# Rover_Power_Supply.net
KiCad netlist of a schematic drawn in EAGLE
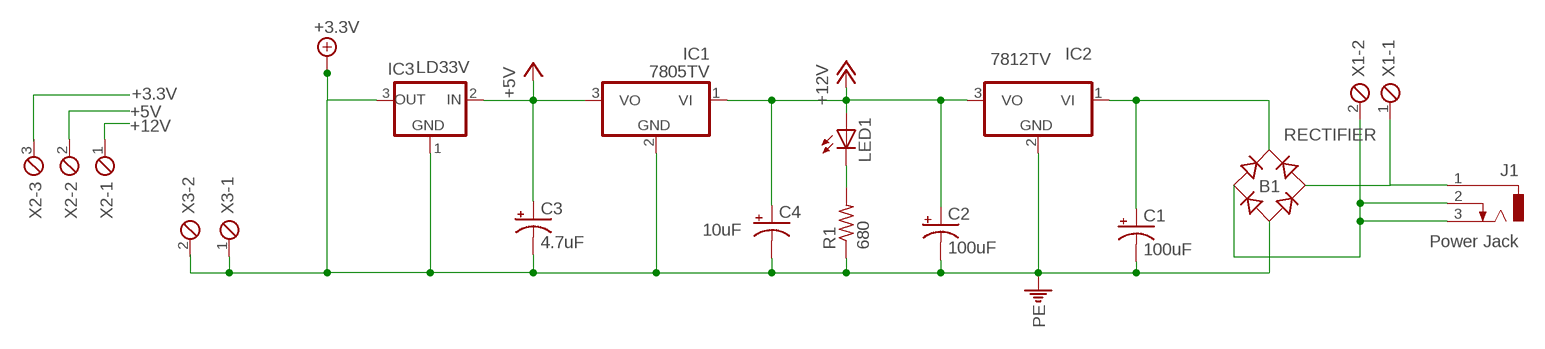
[diagram p0: schematic, sheet 1]

(export (version "E")
  (design (tool "Eeschema 10.0.6"))
  (components
    (comp (ref "B1")
      (value "RECTIFIER")
      (footprint "eagle-import:RB1A")
      (libsource (lib "eagle-import") (part "RB1A"))
    )
    (comp (ref "C1")
      (value "100uF")
      (footprint "eagle-import:E5-8,5")
      (libsource (lib "eagle-import") (part "CPOL-USE5-8.5"))
    )
    (comp (ref "C2")
      (value "100uF")
      (footprint "eagle-import:E5-8,5")
      (libsource (lib "eagle-import") (part "CPOL-USE5-8.5"))
    )
    (comp (ref "C3")
      (value "4.7uF")
      (footprint "eagle-import:E5-8,5")
      (libsource (lib "eagle-import") (part "CPOL-USE5-8.5"))
    )
    (comp (ref "C4")
      (value "10uF")
      (footprint "eagle-import:E5-8,5")
      (libsource (lib "eagle-import") (part "CPOL-USE5-8.5"))
    )
    (comp (ref "IC1")
      (value "7805TV")
      (footprint "eagle-import:TO220V")
      (libsource (lib "eagle-import") (part "78TV05"))
    )
    (comp (ref "IC2")
      (value "7812TV")
      (footprint "eagle-import:TO220V")
      (libsource (lib "eagle-import") (part "78TV12"))
    )
    (comp (ref "IC3")
      (value "LD33V")
      (footprint "eagle-import:78MXXS")
      (libsource (lib "eagle-import") (part "78MXXS"))
    )
    (comp (ref "J1")
      (value "Power Jack")
      (footprint "eagle-import:ROVER-PW-JACL")
      (libsource (lib "eagle-import") (part "DCJ0303"))
    )
    (comp (ref "LED1")
      (value "LED3MM")
      (footprint "eagle-import:LED3MM")
      (libsource (lib "eagle-import") (part "LED3MM"))
    )
    (comp (ref "R1")
      (value "680")
      (footprint "eagle-import:0204_5")
      (libsource (lib "eagle-import") (part "R-US_0204/5"))
    )
    (comp (ref "X1")
      (value "MPT2")
      (footprint "eagle-import:2POL254")
      (libsource (lib "eagle-import") (part "MPT2"))
    )
    (comp (ref "X2")
      (value "MPT3")
      (footprint "eagle-import:3POL254")
      (libsource (lib "eagle-import") (part "MPT3"))
    )
    (comp (ref "X3")
      (value "MPT2")
      (footprint "eagle-import:2POL254")
      (libsource (lib "eagle-import") (part "MPT2"))
    )
  )
  (nets
    (net (code "1") (name "+3.3V") (class "Default")
      (node (ref "B1") (pin "-") (pinfunction "-_-") (pintype "passive"))
      (node (ref "C1") (pin "-") (pinfunction "-_-") (pintype "passive"))
      (node (ref "C2") (pin "-") (pinfunction "-_-") (pintype "passive"))
      (node (ref "C3") (pin "-") (pinfunction "-_-") (pintype "passive"))
      (node (ref "C4") (pin "-") (pinfunction "-_-") (pintype "passive"))
      (node (ref "IC1") (pin "2") (pinfunction "GND_2") (pintype "passive"))
      (node (ref "IC2") (pin "2") (pinfunction "GND_2") (pintype "passive"))
      (node (ref "IC3") (pin "GND") (pinfunction "GND_GND") (pintype "input"))
      (node (ref "IC3") (pin "OUT") (pinfunction "OUT_OUT") (pintype "passive"))
      (node (ref "R1") (pin "1") (pinfunction "1_1") (pintype "passive"))
      (node (ref "X3") (pin "1") (pinfunction "1_1") (pintype "passive"))
    )
    (net (code "2") (name "+5V") (class "Default")
      (node (ref "C3") (pin "+") (pinfunction "+_+") (pintype "passive"))
      (node (ref "IC1") (pin "3") (pinfunction "VO_3") (pintype "passive"))
      (node (ref "X2") (pin "2") (pinfunction "1_2") (pintype "passive"))
    )
    (net (code "3") (name "+12V") (class "Default")
      (node (ref "C2") (pin "+") (pinfunction "+_+") (pintype "passive"))
      (node (ref "C4") (pin "+") (pinfunction "+_+") (pintype "passive"))
      (node (ref "IC1") (pin "1") (pinfunction "VI_1") (pintype "input"))
      (node (ref "IC2") (pin "3") (pinfunction "VO_3") (pintype "passive"))
      (node (ref "LED1") (pin "A") (pinfunction "A_A") (pintype "passive"))
      (node (ref "X2") (pin "1") (pinfunction "1_1") (pintype "passive"))
    )
    (net (code "4") (name "Net-(B1-PadAC1)") (class "Default")
      (node (ref "B1") (pin "AC1") (pinfunction "AC1_AC1") (pintype "passive"))
      (node (ref "J1") (pin "1") (pinfunction "1_1") (pintype "passive"))
      (node (ref "X1") (pin "1") (pinfunction "1_1") (pintype "passive"))
    )
    (net (code "5") (name "Net-(IC2-VI)") (class "Default")
      (node (ref "B1") (pin "+") (pinfunction "+_+") (pintype "passive"))
      (node (ref "C1") (pin "+") (pinfunction "+_+") (pintype "passive"))
      (node (ref "IC2") (pin "1") (pinfunction "VI_1") (pintype "input"))
    )
    (net (code "6") (name "Net-(LED1-C)") (class "Default")
      (node (ref "LED1") (pin "K") (pinfunction "C_K") (pintype "passive"))
      (node (ref "R1") (pin "2") (pinfunction "2_2") (pintype "passive"))
    )
    (net (code "7") (name "Net-(X1B-1)") (class "Default")
      (node (ref "B1") (pin "AC2") (pinfunction "AC2_AC2") (pintype "passive"))
      (node (ref "J1") (pin "2") (pinfunction "2_2") (pintype "passive"))
      (node (ref "J1") (pin "3") (pinfunction "3_3") (pintype "passive"))
      (node (ref "X1") (pin "2") (pinfunction "1_2") (pintype "passive"))
    )
    (net (code "8") (name "unconnected-(IC3-PadIN)") (class "Default")
      (node (ref "IC3") (pin "IN") (pinfunction "IN_IN") (pintype "input"))
    )
    (net (code "9") (name "unconnected-(X2C-1-Pad3)") (class "Default")
      (node (ref "X2") (pin "3") (pinfunction "1_3") (pintype "passive"))
    )
    (net (code "10") (name "unconnected-(X3B-1-Pad2)") (class "Default")
      (node (ref "X3") (pin "2") (pinfunction "1_2") (pintype "passive"))
    )
  )
)
